# main.net
KiCad netlist of a schematic drawn in EAGLE
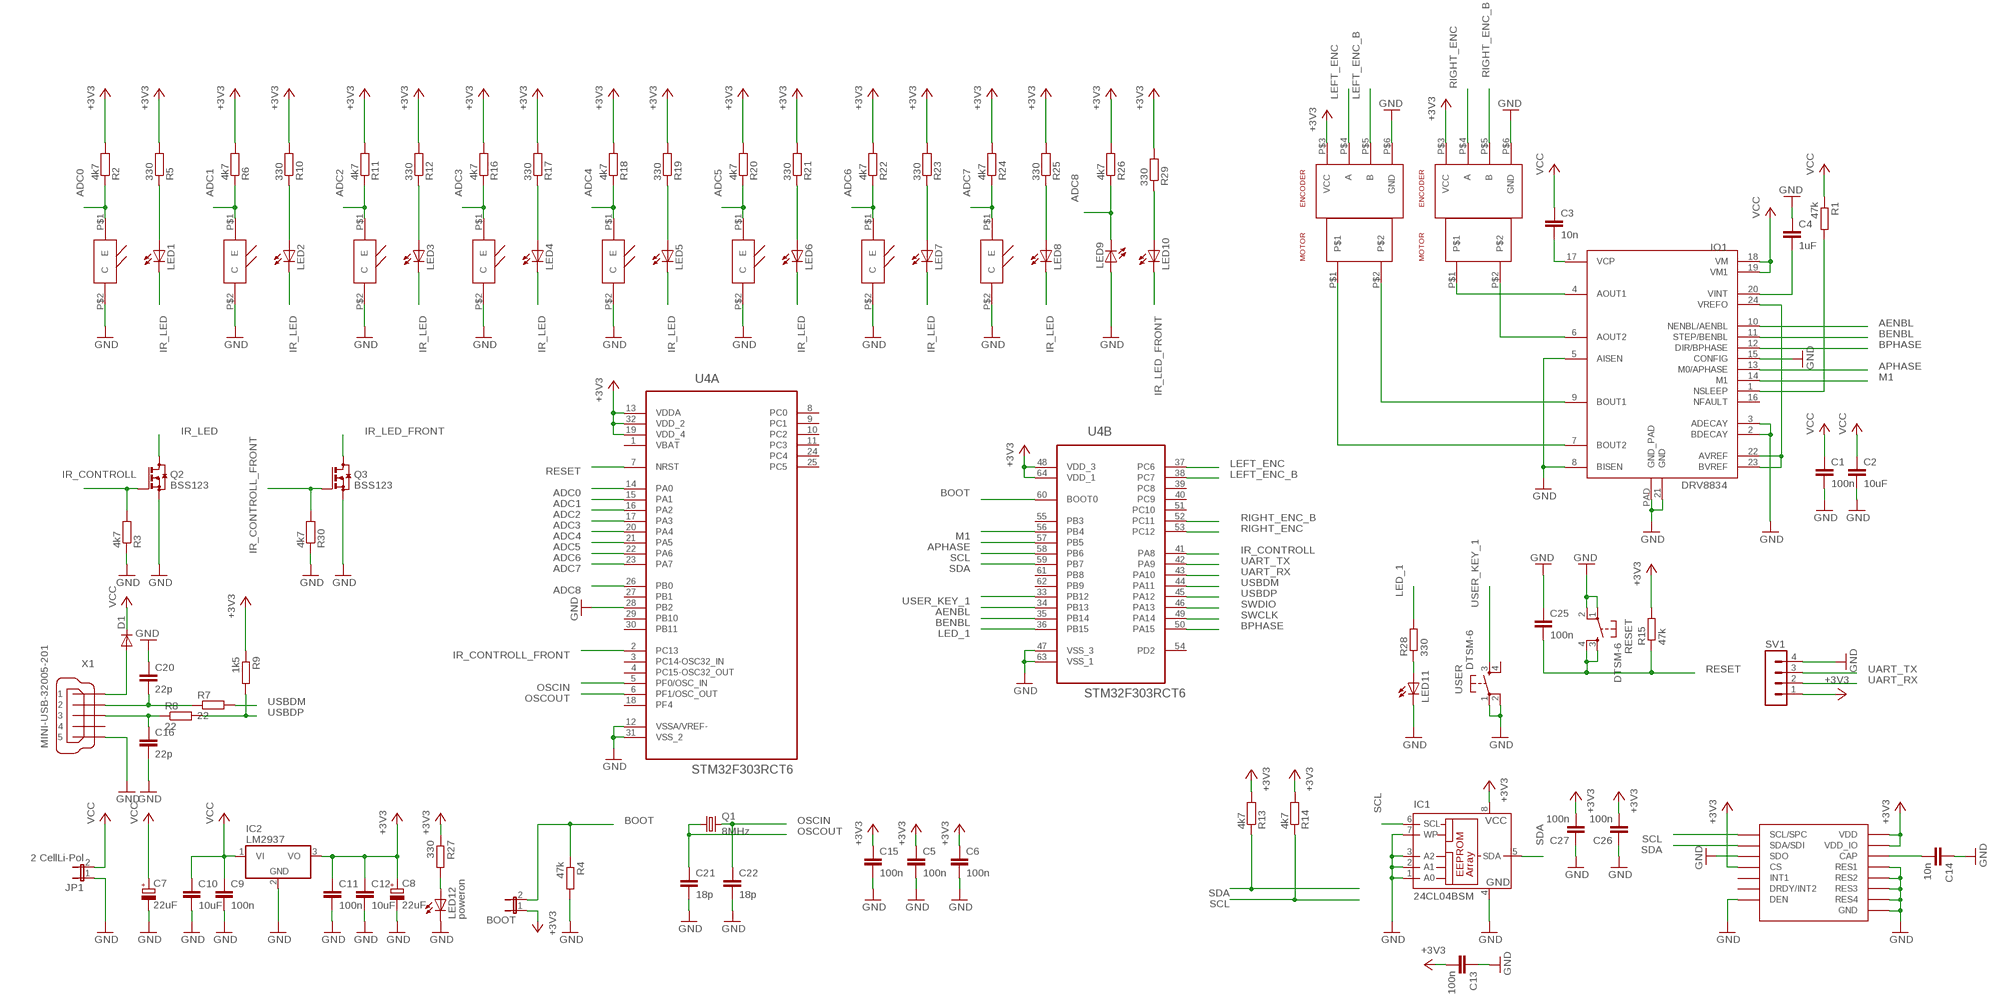
[diagram p0: schematic, sheet 1]

(export (version "E")
  (design (tool "Eeschema 10.0.6"))
  (components
    (comp (ref "BOOT")
      (value "JP1E")
      (footprint "eagle-import:JP1")
      (libsource (lib "eagle-import") (part "JP1E"))
    )
    (comp (ref "C1")
      (value "100n")
      (footprint "eagle-import:C1206")
      (libsource (lib "eagle-import") (part "C-EUC1206"))
    )
    (comp (ref "C2")
      (value "10uF")
      (footprint "eagle-import:C1206")
      (libsource (lib "eagle-import") (part "C-EUC1206"))
    )
    (comp (ref "C3")
      (value "10n")
      (footprint "eagle-import:C1206")
      (libsource (lib "eagle-import") (part "C-EUC1206"))
    )
    (comp (ref "C4")
      (value "1uF")
      (footprint "eagle-import:C1206")
      (libsource (lib "eagle-import") (part "C-EUC1206"))
    )
    (comp (ref "C5")
      (value "100n")
      (footprint "eagle-import:C0805")
      (libsource (lib "eagle-import") (part "C-EUC0805"))
    )
    (comp (ref "C6")
      (value "100n")
      (footprint "eagle-import:C0805")
      (libsource (lib "eagle-import") (part "C-EUC0805"))
    )
    (comp (ref "C7")
      (value "22uF")
      (footprint "eagle-import:153CLV-0505")
      (libsource (lib "eagle-import") (part "CPOL-EU153CLV-0505"))
    )
    (comp (ref "C8")
      (value "22uF")
      (footprint "eagle-import:153CLV-0505")
      (libsource (lib "eagle-import") (part "CPOL-EU153CLV-0505"))
    )
    (comp (ref "C9")
      (value "100n")
      (footprint "eagle-import:C0805")
      (libsource (lib "eagle-import") (part "C-EUC0805"))
    )
    (comp (ref "C10")
      (value "10uF")
      (footprint "eagle-import:C0805")
      (libsource (lib "eagle-import") (part "C-EUC0805"))
    )
    (comp (ref "C11")
      (value "100n")
      (footprint "eagle-import:C0805")
      (libsource (lib "eagle-import") (part "C-EUC0805"))
    )
    (comp (ref "C12")
      (value "10uF")
      (footprint "eagle-import:C0805")
      (libsource (lib "eagle-import") (part "C-EUC0805"))
    )
    (comp (ref "C13")
      (value "100n")
      (footprint "eagle-import:C0805")
      (libsource (lib "eagle-import") (part "C-EUC0805"))
    )
    (comp (ref "C14")
      (value "10n")
      (footprint "eagle-import:C0805")
      (libsource (lib "eagle-import") (part "C-EUC0805"))
    )
    (comp (ref "C15")
      (value "100n")
      (footprint "eagle-import:C0805")
      (libsource (lib "eagle-import") (part "C-EUC0805"))
    )
    (comp (ref "C16")
      (value "22p")
      (footprint "eagle-import:C0805")
      (libsource (lib "eagle-import") (part "C-EUC0805"))
    )
    (comp (ref "C20")
      (value "22p")
      (footprint "eagle-import:C0805")
      (libsource (lib "eagle-import") (part "C-EUC0805"))
    )
    (comp (ref "C21")
      (value "18p")
      (footprint "eagle-import:C0805")
      (libsource (lib "eagle-import") (part "C-EUC0805"))
    )
    (comp (ref "C22")
      (value "18p")
      (footprint "eagle-import:C0805")
      (libsource (lib "eagle-import") (part "C-EUC0805"))
    )
    (comp (ref "C25")
      (value "100n")
      (footprint "eagle-import:C0805")
      (libsource (lib "eagle-import") (part "C-EUC0805"))
    )
    (comp (ref "C26")
      (value "100n")
      (footprint "eagle-import:C0805")
      (libsource (lib "eagle-import") (part "C-EUC0805"))
    )
    (comp (ref "C27")
      (value "100n")
      (footprint "eagle-import:C0805")
      (libsource (lib "eagle-import") (part "C-EUC0805"))
    )
    (comp (ref "D1")
      (value "DIODE-SMB")
      (footprint "eagle-import:SMB")
      (libsource (lib "eagle-import") (part "DIODE-SMB"))
    )
    (comp (ref "IC1")
      (value "24CL04BSM")
      (footprint "eagle-import:SO-08M")
      (fields (field (name "MPN") "FM24CL04-S"))
      (libsource (lib "eagle-import") (part "24SMCL04B"))
    )
    (comp (ref "IC2")
      (value "LM2937")
      (footprint "eagle-import:TO263-3")
      (libsource (lib "eagle-import") (part "LM2937"))
    )
    (comp (ref "IO1")
      (value "DRV8834")
      (footprint "eagle-import:DRV8834_PCK")
      (libsource (lib "eagle-import") (part "DRV8834"))
    )
    (comp (ref "JP1")
      (value "2 CellLi-Pol")
      (footprint "eagle-import:JP1")
      (libsource (lib "eagle-import") (part "JP1E"))
    )
    (comp (ref "LED1")
      (value "LEDCHIPLED_1206")
      (footprint "eagle-import:CHIPLED_1206")
      (libsource (lib "eagle-import") (part "LEDCHIPLED_1206"))
    )
    (comp (ref "LED2")
      (value "LEDCHIPLED_1206")
      (footprint "eagle-import:CHIPLED_1206")
      (libsource (lib "eagle-import") (part "LEDCHIPLED_1206"))
    )
    (comp (ref "LED3")
      (value "LEDCHIPLED_1206")
      (footprint "eagle-import:CHIPLED_1206")
      (libsource (lib "eagle-import") (part "LEDCHIPLED_1206"))
    )
    (comp (ref "LED4")
      (value "LEDCHIPLED_1206")
      (footprint "eagle-import:CHIPLED_1206")
      (libsource (lib "eagle-import") (part "LEDCHIPLED_1206"))
    )
    (comp (ref "LED5")
      (value "LEDCHIPLED_1206")
      (footprint "eagle-import:CHIPLED_1206")
      (libsource (lib "eagle-import") (part "LEDCHIPLED_1206"))
    )
    (comp (ref "LED6")
      (value "LEDCHIPLED_1206")
      (footprint "eagle-import:CHIPLED_1206")
      (libsource (lib "eagle-import") (part "LEDCHIPLED_1206"))
    )
    (comp (ref "LED7")
      (value "LEDCHIPLED_1206")
      (footprint "eagle-import:CHIPLED_1206")
      (libsource (lib "eagle-import") (part "LEDCHIPLED_1206"))
    )
    (comp (ref "LED8")
      (value "LEDCHIPLED_1206")
      (footprint "eagle-import:CHIPLED_1206")
      (libsource (lib "eagle-import") (part "LEDCHIPLED_1206"))
    )
    (comp (ref "LED9")
      (value "LED5MM")
      (footprint "eagle-import:LED5MM")
      (libsource (lib "eagle-import") (part "my_parts_LED5MM"))
    )
    (comp (ref "LED10")
      (value "LED5MM")
      (footprint "eagle-import:LED5MM")
      (libsource (lib "eagle-import") (part "my_parts_LED5MM"))
    )
    (comp (ref "LED11")
      (value "LEDCHIPLED_1206")
      (footprint "eagle-import:CHIPLED_1206")
      (libsource (lib "eagle-import") (part "LEDCHIPLED_1206"))
    )
    (comp (ref "LED12")
      (value "poweron")
      (footprint "eagle-import:CHIPLED_1206")
      (libsource (lib "eagle-import") (part "LEDCHIPLED_1206"))
    )
    (comp (ref "LSM6DS0")
      (value "L3GD20H")
      (footprint "eagle-import:LGA16L")
      (libsource (lib "eagle-import") (part "L3GD20H"))
    )
    (comp (ref "Q1")
      (value "8MHz")
      (footprint "eagle-import:CTS406")
      (libsource (lib "eagle-import") (part "CRYSTALCTS406"))
    )
    (comp (ref "Q2")
      (value "BSS123")
      (footprint "eagle-import:SOT23")
      (libsource (lib "eagle-import") (part "BSS123"))
    )
    (comp (ref "Q3")
      (value "BSS123")
      (footprint "eagle-import:SOT23")
      (libsource (lib "eagle-import") (part "BSS123"))
    )
    (comp (ref "R1")
      (value "47k")
      (footprint "eagle-import:M1206")
      (libsource (lib "eagle-import") (part "R-EU_M1206"))
    )
    (comp (ref "R2")
      (value "4k7")
      (footprint "eagle-import:M0805")
      (libsource (lib "eagle-import") (part "R-EU_M0805"))
    )
    (comp (ref "R3")
      (value "4k7")
      (footprint "eagle-import:M0805")
      (libsource (lib "eagle-import") (part "R-EU_M0805"))
    )
    (comp (ref "R4")
      (value "47k")
      (footprint "eagle-import:M0805")
      (libsource (lib "eagle-import") (part "R-EU_M0805"))
    )
    (comp (ref "R5")
      (value "330")
      (footprint "eagle-import:M0805")
      (libsource (lib "eagle-import") (part "R-EU_M0805"))
    )
    (comp (ref "R6")
      (value "4k7")
      (footprint "eagle-import:M0805")
      (libsource (lib "eagle-import") (part "R-EU_M0805"))
    )
    (comp (ref "R7")
      (value "22")
      (footprint "eagle-import:M0805")
      (libsource (lib "eagle-import") (part "R-EU_M0805"))
    )
    (comp (ref "R8")
      (value "22")
      (footprint "eagle-import:M0805")
      (libsource (lib "eagle-import") (part "R-EU_M0805"))
    )
    (comp (ref "R9")
      (value "1k5")
      (footprint "eagle-import:M0805")
      (libsource (lib "eagle-import") (part "R-EU_M0805"))
    )
    (comp (ref "R10")
      (value "330")
      (footprint "eagle-import:M0805")
      (libsource (lib "eagle-import") (part "R-EU_M0805"))
    )
    (comp (ref "R11")
      (value "4k7")
      (footprint "eagle-import:M0805")
      (libsource (lib "eagle-import") (part "R-EU_M0805"))
    )
    (comp (ref "R12")
      (value "330")
      (footprint "eagle-import:M0805")
      (libsource (lib "eagle-import") (part "R-EU_M0805"))
    )
    (comp (ref "R13")
      (value "4k7")
      (footprint "eagle-import:M0805")
      (libsource (lib "eagle-import") (part "R-EU_M0805"))
    )
    (comp (ref "R14")
      (value "4k7")
      (footprint "eagle-import:M0805")
      (libsource (lib "eagle-import") (part "R-EU_M0805"))
    )
    (comp (ref "R15")
      (value "47k")
      (footprint "eagle-import:M0805")
      (libsource (lib "eagle-import") (part "R-EU_M0805"))
    )
    (comp (ref "R16")
      (value "4k7")
      (footprint "eagle-import:M0805")
      (libsource (lib "eagle-import") (part "R-EU_M0805"))
    )
    (comp (ref "R17")
      (value "330")
      (footprint "eagle-import:M0805")
      (libsource (lib "eagle-import") (part "R-EU_M0805"))
    )
    (comp (ref "R18")
      (value "4k7")
      (footprint "eagle-import:M0805")
      (libsource (lib "eagle-import") (part "R-EU_M0805"))
    )
    (comp (ref "R19")
      (value "330")
      (footprint "eagle-import:M0805")
      (libsource (lib "eagle-import") (part "R-EU_M0805"))
    )
    (comp (ref "R20")
      (value "4k7")
      (footprint "eagle-import:M0805")
      (libsource (lib "eagle-import") (part "R-EU_M0805"))
    )
    (comp (ref "R21")
      (value "330")
      (footprint "eagle-import:M0805")
      (libsource (lib "eagle-import") (part "R-EU_M0805"))
    )
    (comp (ref "R22")
      (value "4k7")
      (footprint "eagle-import:M0805")
      (libsource (lib "eagle-import") (part "R-EU_M0805"))
    )
    (comp (ref "R23")
      (value "330")
      (footprint "eagle-import:M0805")
      (libsource (lib "eagle-import") (part "R-EU_M0805"))
    )
    (comp (ref "R24")
      (value "4k7")
      (footprint "eagle-import:M0805")
      (libsource (lib "eagle-import") (part "R-EU_M0805"))
    )
    (comp (ref "R25")
      (value "330")
      (footprint "eagle-import:M0805")
      (libsource (lib "eagle-import") (part "R-EU_M0805"))
    )
    (comp (ref "R26")
      (value "4k7")
      (footprint "eagle-import:M0805")
      (libsource (lib "eagle-import") (part "R-EU_M0805"))
    )
    (comp (ref "R27")
      (value "330")
      (footprint "eagle-import:M0805")
      (libsource (lib "eagle-import") (part "R-EU_M0805"))
    )
    (comp (ref "R28")
      (value "330")
      (footprint "eagle-import:M0805")
      (libsource (lib "eagle-import") (part "R-EU_M0805"))
    )
    (comp (ref "R29")
      (value "330")
      (footprint "eagle-import:M0805")
      (libsource (lib "eagle-import") (part "R-EU_M0805"))
    )
    (comp (ref "R30")
      (value "4k7")
      (footprint "eagle-import:M0805")
      (libsource (lib "eagle-import") (part "R-EU_M0805"))
    )
    (comp (ref "RESET")
      (value "DTSM-6")
      (footprint "eagle-import:DTSM-6")
      (libsource (lib "eagle-import") (part "DTSM-6"))
    )
    (comp (ref "SV1")
      (value "MA04-1")
      (footprint "eagle-import:MA04-1")
      (libsource (lib "eagle-import") (part "MA04-1"))
    )
    (comp (ref "U$3")
      (value "SFH3710")
      (footprint "eagle-import:SFH3710")
      (libsource (lib "eagle-import") (part "SFH3710"))
    )
    (comp (ref "U$4")
      (value "SFH3710")
      (footprint "eagle-import:SFH3710")
      (libsource (lib "eagle-import") (part "SFH3710"))
    )
    (comp (ref "U$5")
      (value "SFH3710")
      (footprint "eagle-import:SFH3710")
      (libsource (lib "eagle-import") (part "SFH3710"))
    )
    (comp (ref "U$6")
      (value "SFH3710")
      (footprint "eagle-import:SFH3710")
      (libsource (lib "eagle-import") (part "SFH3710"))
    )
    (comp (ref "U$7")
      (value "SFH3710")
      (footprint "eagle-import:SFH3710")
      (libsource (lib "eagle-import") (part "SFH3710"))
    )
    (comp (ref "U$8")
      (value "SFH3710")
      (footprint "eagle-import:SFH3710")
      (libsource (lib "eagle-import") (part "SFH3710"))
    )
    (comp (ref "U$9")
      (value "SFH3710")
      (footprint "eagle-import:SFH3710")
      (libsource (lib "eagle-import") (part "SFH3710"))
    )
    (comp (ref "U$10")
      (value "SFH3710")
      (footprint "eagle-import:SFH3710")
      (libsource (lib "eagle-import") (part "SFH3710"))
    )
    (comp (ref "U$11")
      (value "POLOLU_GEAR_MOTORPOLO")
      (footprint "eagle-import:POLOLU_GEAR_MOTOR")
      (libsource (lib "eagle-import") (part "POLOLU_GEAR_MOTORPOLO"))
    )
    (comp (ref "U$12")
      (value "POLOLU_GEAR_MOTORPOLO")
      (footprint "eagle-import:POLOLU_GEAR_MOTOR")
      (libsource (lib "eagle-import") (part "POLOLU_GEAR_MOTORPOLO"))
    )
    (comp (ref "U4")
      (value "STM32F303RCT6")
      (footprint "eagle-import:QFP50P1200X1200X160-64N")
      (libsource (lib "eagle-import") (part "STM32F303RCT6"))
    )
    (comp (ref "USER")
      (value "DTSM-6")
      (footprint "eagle-import:DTSM-6")
      (libsource (lib "eagle-import") (part "DTSM-6"))
    )
    (comp (ref "X1")
      (value "MINI-USB-32005-201")
      (footprint "eagle-import:32005-201")
      (libsource (lib "eagle-import") (part "MINI-USB-32005-201"))
    )
  )
  (nets
    (net (code "1") (name "+3V3") (class "Default")
      (node (ref "BOOT") (pin "1") (pinfunction "1_1") (pintype "passive"))
      (node (ref "C11") (pin "1") (pinfunction "1_1") (pintype "passive"))
      (node (ref "C12") (pin "1") (pinfunction "1_1") (pintype "passive"))
      (node (ref "C13") (pin "2") (pinfunction "2_2") (pintype "passive"))
      (node (ref "C15") (pin "1") (pinfunction "1_1") (pintype "passive"))
      (node (ref "C26") (pin "2") (pinfunction "2_2") (pintype "passive"))
      (node (ref "C27") (pin "2") (pinfunction "2_2") (pintype "passive"))
      (node (ref "C5") (pin "1") (pinfunction "1_1") (pintype "passive"))
      (node (ref "C6") (pin "1") (pinfunction "1_1") (pintype "passive"))
      (node (ref "C8") (pin "+") (pinfunction "+_+") (pintype "passive"))
      (node (ref "IC1") (pin "8") (pinfunction "VCC_8") (pintype "power_in"))
      (node (ref "IC2") (pin "3") (pinfunction "VO_3") (pintype "passive"))
      (node (ref "LSM6DS0") (pin "P$1") (pinfunction "VDD_IO_P$1") (pintype "power_in"))
      (node (ref "LSM6DS0") (pin "P$16") (pinfunction "VDD_P$16") (pintype "power_in"))
      (node (ref "LSM6DS0") (pin "P$5") (pinfunction "CS_P$5") (pintype "bidirectional"))
      (node (ref "R10") (pin "2") (pinfunction "2_2") (pintype "passive"))
      (node (ref "R11") (pin "2") (pinfunction "2_2") (pintype "passive"))
      (node (ref "R12") (pin "2") (pinfunction "2_2") (pintype "passive"))
      (node (ref "R13") (pin "2") (pinfunction "2_2") (pintype "passive"))
      (node (ref "R14") (pin "2") (pinfunction "2_2") (pintype "passive"))
      (node (ref "R15") (pin "2") (pinfunction "2_2") (pintype "passive"))
      (node (ref "R16") (pin "2") (pinfunction "2_2") (pintype "passive"))
      (node (ref "R17") (pin "2") (pinfunction "2_2") (pintype "passive"))
      (node (ref "R18") (pin "2") (pinfunction "2_2") (pintype "passive"))
      (node (ref "R19") (pin "2") (pinfunction "2_2") (pintype "passive"))
      (node (ref "R2") (pin "2") (pinfunction "2_2") (pintype "passive"))
      (node (ref "R20") (pin "2") (pinfunction "2_2") (pintype "passive"))
      (node (ref "R21") (pin "2") (pinfunction "2_2") (pintype "passive"))
      (node (ref "R22") (pin "2") (pinfunction "2_2") (pintype "passive"))
      (node (ref "R23") (pin "2") (pinfunction "2_2") (pintype "passive"))
      (node (ref "R24") (pin "2") (pinfunction "2_2") (pintype "passive"))
      (node (ref "R25") (pin "2") (pinfunction "2_2") (pintype "passive"))
      (node (ref "R26") (pin "2") (pinfunction "2_2") (pintype "passive"))
      (node (ref "R27") (pin "1") (pinfunction "1_1") (pintype "passive"))
      (node (ref "R29") (pin "2") (pinfunction "2_2") (pintype "passive"))
      (node (ref "R5") (pin "2") (pinfunction "2_2") (pintype "passive"))
      (node (ref "R6") (pin "2") (pinfunction "2_2") (pintype "passive"))
      (node (ref "R9") (pin "1") (pinfunction "1_1") (pintype "passive"))
      (node (ref "SV1") (pin "1") (pinfunction "1_1") (pintype "passive"))
      (node (ref "U$11") (pin "P$3") (pinfunction "VCC_P$3") (pintype "bidirectional"))
      (node (ref "U$12") (pin "P$3") (pinfunction "VCC_P$3") (pintype "bidirectional"))
      (node (ref "U4") (pin "13") (pinfunction "VDDA_13") (pintype "power_in"))
      (node (ref "U4") (pin "19") (pinfunction "VDD_4_19") (pintype "power_in"))
      (node (ref "U4") (pin "32") (pinfunction "VDD_2_32") (pintype "power_in"))
      (node (ref "U4") (pin "48") (pinfunction "VDD_3_48") (pintype "power_in"))
      (node (ref "U4") (pin "64") (pinfunction "VDD_1_64") (pintype "power_in"))
    )
    (net (code "2") (name "/ADC0") (class "Default")
      (node (ref "R2") (pin "1") (pinfunction "1_1") (pintype "passive"))
      (node (ref "U$3") (pin "P$1") (pinfunction "E_P$1") (pintype "bidirectional"))
      (node (ref "U4") (pin "14") (pinfunction "PA0_14") (pintype "bidirectional"))
    )
    (net (code "3") (name "/ADC1") (class "Default")
      (node (ref "R6") (pin "1") (pinfunction "1_1") (pintype "passive"))
      (node (ref "U$4") (pin "P$1") (pinfunction "E_P$1") (pintype "bidirectional"))
      (node (ref "U4") (pin "15") (pinfunction "PA1_15") (pintype "bidirectional"))
    )
    (net (code "4") (name "/ADC2") (class "Default")
      (node (ref "R11") (pin "1") (pinfunction "1_1") (pintype "passive"))
      (node (ref "U$5") (pin "P$1") (pinfunction "E_P$1") (pintype "bidirectional"))
      (node (ref "U4") (pin "16") (pinfunction "PA2_16") (pintype "bidirectional"))
    )
    (net (code "5") (name "/ADC3") (class "Default")
      (node (ref "R16") (pin "1") (pinfunction "1_1") (pintype "passive"))
      (node (ref "U$6") (pin "P$1") (pinfunction "E_P$1") (pintype "bidirectional"))
      (node (ref "U4") (pin "17") (pinfunction "PA3_17") (pintype "bidirectional"))
    )
    (net (code "6") (name "/ADC4") (class "Default")
      (node (ref "R18") (pin "1") (pinfunction "1_1") (pintype "passive"))
      (node (ref "U$7") (pin "P$1") (pinfunction "E_P$1") (pintype "bidirectional"))
      (node (ref "U4") (pin "20") (pinfunction "PA4_20") (pintype "bidirectional"))
    )
    (net (code "7") (name "/ADC5") (class "Default")
      (node (ref "R20") (pin "1") (pinfunction "1_1") (pintype "passive"))
      (node (ref "U$8") (pin "P$1") (pinfunction "E_P$1") (pintype "bidirectional"))
      (node (ref "U4") (pin "21") (pinfunction "PA5_21") (pintype "bidirectional"))
    )
    (net (code "8") (name "/ADC6") (class "Default")
      (node (ref "R22") (pin "1") (pinfunction "1_1") (pintype "passive"))
      (node (ref "U$9") (pin "P$1") (pinfunction "E_P$1") (pintype "bidirectional"))
      (node (ref "U4") (pin "22") (pinfunction "PA6_22") (pintype "bidirectional"))
    )
    (net (code "9") (name "/ADC7") (class "Default")
      (node (ref "R24") (pin "1") (pinfunction "1_1") (pintype "passive"))
      (node (ref "U$10") (pin "P$1") (pinfunction "E_P$1") (pintype "bidirectional"))
      (node (ref "U4") (pin "23") (pinfunction "PA7_23") (pintype "bidirectional"))
    )
    (net (code "10") (name "/ADC8") (class "Default")
      (node (ref "LED9") (pin "K") (pinfunction "C_K") (pintype "passive"))
      (node (ref "R26") (pin "1") (pinfunction "1_1") (pintype "passive"))
      (node (ref "U4") (pin "26") (pinfunction "PB0_26") (pintype "bidirectional"))
    )
    (net (code "11") (name "/AENBL") (class "Default")
      (node (ref "IO1") (pin "10") (pinfunction "NENBL/AENBL_10") (pintype "bidirectional"))
      (node (ref "U4") (pin "34") (pinfunction "PB13_34") (pintype "bidirectional"))
    )
    (net (code "12") (name "/APHASE") (class "Default")
      (node (ref "IO1") (pin "13") (pinfunction "M0/APHASE_13") (pintype "bidirectional"))
      (node (ref "U4") (pin "57") (pinfunction "PB5_57") (pintype "bidirectional"))
    )
    (net (code "13") (name "/BENBL") (class "Default")
      (node (ref "IO1") (pin "11") (pinfunction "STEP/BENBL_11") (pintype "bidirectional"))
      (node (ref "U4") (pin "35") (pinfunction "PB14_35") (pintype "bidirectional"))
    )
    (net (code "14") (name "/BOOT") (class "Default")
      (node (ref "BOOT") (pin "2") (pinfunction "2_2") (pintype "passive"))
      (node (ref "R4") (pin "1") (pinfunction "1_1") (pintype "passive"))
      (node (ref "U4") (pin "60") (pinfunction "BOOT0_60") (pintype "input"))
    )
    (net (code "15") (name "/BPHASE") (class "Default")
      (node (ref "IO1") (pin "12") (pinfunction "DIR/BPHASE_12") (pintype "bidirectional"))
      (node (ref "U4") (pin "50") (pinfunction "PA15_50") (pintype "bidirectional"))
    )
    (net (code "16") (name "/IR_CONTROLL") (class "Default")
      (node (ref "Q2") (pin "1") (pinfunction "G_1") (pintype "passive"))
      (node (ref "R3") (pin "2") (pinfunction "2_2") (pintype "passive"))
      (node (ref "U4") (pin "41") (pinfunction "PA8_41") (pintype "bidirectional"))
    )
    (net (code "17") (name "/IR_CONTROLL_FRONT") (class "Default")
      (node (ref "Q3") (pin "1") (pinfunction "G_1") (pintype "passive"))
      (node (ref "R30") (pin "2") (pinfunction "2_2") (pintype "passive"))
      (node (ref "U4") (pin "2") (pinfunction "PC13_2") (pintype "bidirectional"))
    )
    (net (code "18") (name "/IR_LED") (class "Default")
      (node (ref "LED1") (pin "C") (pinfunction "C_C") (pintype "passive"))
      (node (ref "LED2") (pin "C") (pinfunction "C_C") (pintype "passive"))
      (node (ref "LED3") (pin "C") (pinfunction "C_C") (pintype "passive"))
      (node (ref "LED4") (pin "C") (pinfunction "C_C") (pintype "passive"))
      (node (ref "LED5") (pin "C") (pinfunction "C_C") (pintype "passive"))
      (node (ref "LED6") (pin "C") (pinfunction "C_C") (pintype "passive"))
      (node (ref "LED7") (pin "C") (pinfunction "C_C") (pintype "passive"))
      (node (ref "LED8") (pin "C") (pinfunction "C_C") (pintype "passive"))
      (node (ref "Q2") (pin "3") (pinfunction "D_3") (pintype "passive"))
    )
    (net (code "19") (name "/IR_LED_FRONT") (class "Default")
      (node (ref "LED10") (pin "K") (pinfunction "C_K") (pintype "passive"))
      (node (ref "Q3") (pin "3") (pinfunction "D_3") (pintype "passive"))
    )
    (net (code "20") (name "/LED_1") (class "Default")
      (node (ref "R28") (pin "2") (pinfunction "2_2") (pintype "passive"))
      (node (ref "U4") (pin "36") (pinfunction "PB15_36") (pintype "bidirectional"))
    )
    (net (code "21") (name "/LEFT_ENC") (class "Default")
      (node (ref "U$11") (pin "P$4") (pinfunction "A_P$4") (pintype "bidirectional"))
      (node (ref "U4") (pin "37") (pinfunction "PC6_37") (pintype "bidirectional"))
    )
    (net (code "22") (name "/LEFT_ENC_B") (class "Default")
      (node (ref "U$11") (pin "P$5") (pinfunction "B_P$5") (pintype "bidirectional"))
      (node (ref "U4") (pin "38") (pinfunction "PC7_38") (pintype "bidirectional"))
    )
    (net (code "23") (name "/M1") (class "Default")
      (node (ref "IO1") (pin "14") (pinfunction "M1_14") (pintype "bidirectional"))
      (node (ref "U4") (pin "56") (pinfunction "PB4_56") (pintype "bidirectional"))
    )
    (net (code "24") (name "/OSCIN") (class "Default")
      (node (ref "C22") (pin "1") (pinfunction "1_1") (pintype "passive"))
      (node (ref "Q1") (pin "3") (pinfunction "2_3") (pintype "passive"))
      (node (ref "U4") (pin "5") (pinfunction "PF0/OSC_IN_5") (pintype "bidirectional"))
    )
    (net (code "25") (name "/OSCOUT") (class "Default")
      (node (ref "C21") (pin "1") (pinfunction "1_1") (pintype "passive"))
      (node (ref "Q1") (pin "1") (pinfunction "1_1") (pintype "passive"))
      (node (ref "U4") (pin "6") (pinfunction "PF1/OSC_OUT_6") (pintype "bidirectional"))
    )
    (net (code "26") (name "/RESET") (class "Default")
      (node (ref "C25") (pin "2") (pinfunction "2_2") (pintype "passive"))
      (node (ref "R15") (pin "1") (pinfunction "1_1") (pintype "passive"))
      (node (ref "RESET") (pin "3") (pinfunction "3_3") (pintype "passive"))
      (node (ref "RESET") (pin "4") (pinfunction "4_4") (pintype "passive"))
      (node (ref "U4") (pin "7") (pinfunction "NRST_7") (pintype "bidirectional"))
    )
    (net (code "27") (name "/RIGHT_ENC") (class "Default")
      (node (ref "U$12") (pin "P$4") (pinfunction "A_P$4") (pintype "bidirectional"))
      (node (ref "U4") (pin "53") (pinfunction "PC12_53") (pintype "bidirectional"))
    )
    (net (code "28") (name "/RIGHT_ENC_B") (class "Default")
      (node (ref "U$12") (pin "P$5") (pinfunction "B_P$5") (pintype "bidirectional"))
      (node (ref "U4") (pin "52") (pinfunction "PC11_52") (pintype "bidirectional"))
    )
    (net (code "29") (name "/SCL") (class "Default")
      (node (ref "IC1") (pin "6") (pinfunction "SCL_6") (pintype "input"))
      (node (ref "LSM6DS0") (pin "P$2") (pinfunction "SCL/SPC_P$2") (pintype "bidirectional"))
      (node (ref "R14") (pin "1") (pinfunction "1_1") (pintype "passive"))
      (node (ref "U4") (pin "58") (pinfunction "PB6_58") (pintype "bidirectional"))
    )
    (net (code "30") (name "/SDA") (class "Default")
      (node (ref "IC1") (pin "5") (pinfunction "SDA_5") (pintype "bidirectional"))
      (node (ref "LSM6DS0") (pin "P$3") (pinfunction "SDA/SDI_P$3") (pintype "bidirectional"))
      (node (ref "R13") (pin "1") (pinfunction "1_1") (pintype "passive"))
      (node (ref "U4") (pin "59") (pinfunction "PB7_59") (pintype "bidirectional"))
    )
    (net (code "31") (name "/SWCLK") (class "Default")
      (node (ref "U4") (pin "49") (pinfunction "PA14_49") (pintype "bidirectional"))
    )
    (net (code "32") (name "/SWDIO") (class "Default")
      (node (ref "U4") (pin "46") (pinfunction "PA13_46") (pintype "bidirectional"))
    )
    (net (code "33") (name "/UART_RX") (class "Default")
      (node (ref "SV1") (pin "2") (pinfunction "2_2") (pintype "passive"))
      (node (ref "U4") (pin "43") (pinfunction "PA10_43") (pintype "bidirectional"))
    )
    (net (code "34") (name "/UART_TX") (class "Default")
      (node (ref "SV1") (pin "3") (pinfunction "3_3") (pintype "passive"))
      (node (ref "U4") (pin "42") (pinfunction "PA9_42") (pintype "bidirectional"))
    )
    (net (code "35") (name "/USBDM") (class "Default")
      (node (ref "R7") (pin "2") (pinfunction "2_2") (pintype "passive"))
      (node (ref "U4") (pin "44") (pinfunction "PA11_44") (pintype "bidirectional"))
    )
    (net (code "36") (name "/USBDP") (class "Default")
      (node (ref "R8") (pin "2") (pinfunction "2_2") (pintype "passive"))
      (node (ref "R9") (pin "2") (pinfunction "2_2") (pintype "passive"))
      (node (ref "U4") (pin "45") (pinfunction "PA12_45") (pintype "bidirectional"))
    )
    (net (code "37") (name "/USER_KEY_1") (class "Default")
      (node (ref "U4") (pin "33") (pinfunction "PB12_33") (pintype "bidirectional"))
      (node (ref "USER") (pin "3") (pinfunction "3_3") (pintype "passive"))
    )
    (net (code "38") (name "/VBAT") (class "Default")
      (node (ref "U4") (pin "1") (pinfunction "VBAT_1") (pintype "power_in"))
    )
    (net (code "39") (name "GND") (class "Default")
      (node (ref "C1") (pin "2") (pinfunction "2_2") (pintype "passive"))
      (node (ref "C10") (pin "2") (pinfunction "2_2") (pintype "passive"))
      (node (ref "C11") (pin "2") (pinfunction "2_2") (pintype "passive"))
      (node (ref "C12") (pin "2") (pinfunction "2_2") (pintype "passive"))
      (node (ref "C13") (pin "1") (pinfunction "1_1") (pintype "passive"))
      (node (ref "C14") (pin "1") (pinfunction "1_1") (pintype "passive"))
      (node (ref "C15") (pin "2") (pinfunction "2_2") (pintype "passive"))
      (node (ref "C16") (pin "2") (pinfunction "2_2") (pintype "passive"))
      (node (ref "C2") (pin "2") (pinfunction "2_2") (pintype "passive"))
      (node (ref "C20") (pin "1") (pinfunction "1_1") (pintype "passive"))
      (node (ref "C21") (pin "2") (pinfunction "2_2") (pintype "passive"))
      (node (ref "C22") (pin "2") (pinfunction "2_2") (pintype "passive"))
      (node (ref "C25") (pin "1") (pinfunction "1_1") (pintype "passive"))
      (node (ref "C26") (pin "1") (pinfunction "1_1") (pintype "passive"))
      (node (ref "C27") (pin "1") (pinfunction "1_1") (pintype "passive"))
      (node (ref "C4") (pin "1") (pinfunction "1_1") (pintype "passive"))
      (node (ref "C5") (pin "2") (pinfunction "2_2") (pintype "passive"))
      (node (ref "C6") (pin "2") (pinfunction "2_2") (pintype "passive"))
      (node (ref "C7") (pin "-") (pinfunction "-_-") (pintype "passive"))
      (node (ref "C8") (pin "-") (pinfunction "-_-") (pintype "passive"))
      (node (ref "C9") (pin "2") (pinfunction "2_2") (pintype "passive"))
      (node (ref "IC1") (pin "1") (pinfunction "A0_1") (pintype "input"))
      (node (ref "IC1") (pin "2") (pinfunction "A1_2") (pintype "input"))
      (node (ref "IC1") (pin "3") (pinfunction "A2_3") (pintype "input"))
      (node (ref "IC1") (pin "4") (pinfunction "GND_4") (pintype "power_in"))
      (node (ref "IC1") (pin "7") (pinfunction "WP_7") (pintype "input"))
      (node (ref "IC2") (pin "2") (pinfunction "GND_2") (pintype "passive"))
      (node (ref "IO1") (pin "15") (pinfunction "CONFIG_15") (pintype "bidirectional"))
      (node (ref "IO1") (pin "2") (pinfunction "BDECAY_2") (pintype "bidirectional"))
      (node (ref "IO1") (pin "21") (pinfunction "GND_21") (pintype "bidirectional"))
      (node (ref "IO1") (pin "3") (pinfunction "ADECAY_3") (pintype "bidirectional"))
      (node (ref "IO1") (pin "5") (pinfunction "AISEN_5") (pintype "bidirectional"))
      (node (ref "IO1") (pin "8") (pinfunction "BISEN_8") (pintype "bidirectional"))
      (node (ref "IO1") (pin "PAD") (pinfunction "GND_PAD_PAD") (pintype "bidirectional"))
      (node (ref "JP1") (pin "1") (pinfunction "1_1") (pintype "passive"))
      (node (ref "LED11") (pin "C") (pinfunction "C_C") (pintype "passive"))
      (node (ref "LED12") (pin "C") (pinfunction "C_C") (pintype "passive"))
      (node (ref "LED9") (pin "A") (pinfunction "A_A") (pintype "passive"))
      (node (ref "LSM6DS0") (pin "P$10") (pinfunction "RES2_P$10") (pintype "bidirectional"))
      (node (ref "LSM6DS0") (pin "P$11") (pinfunction "RES3_P$11") (pintype "bidirectional"))
      (node (ref "LSM6DS0") (pin "P$12") (pinfunction "GND_P$12") (pintype "power_in"))
      (node (ref "LSM6DS0") (pin "P$13") (pinfunction "GND_P$13") (pintype "power_in"))
      (node (ref "LSM6DS0") (pin "P$15") (pinfunction "RES4_P$15") (pintype "bidirectional"))
      (node (ref "LSM6DS0") (pin "P$4") (pinfunction "SDO_P$4") (pintype "bidirectional"))
      (node (ref "LSM6DS0") (pin "P$8") (pinfunction "DEN_P$8") (pintype "bidirectional"))
      (node (ref "LSM6DS0") (pin "P$9") (pinfunction "RES1_P$9") (pintype "bidirectional"))
      (node (ref "Q2") (pin "2") (pinfunction "S_2") (pintype "passive"))
      (node (ref "Q3") (pin "2") (pinfunction "S_2") (pintype "passive"))
      (node (ref "R3") (pin "1") (pinfunction "1_1") (pintype "passive"))
      (node (ref "R30") (pin "1") (pinfunction "1_1") (pintype "passive"))
      (node (ref "R4") (pin "2") (pinfunction "2_2") (pintype "passive"))
      (node (ref "RESET") (pin "1") (pinfunction "1_1") (pintype "passive"))
      (node (ref "RESET") (pin "2") (pinfunction "2_2") (pintype "passive"))
      (node (ref "SV1") (pin "4") (pinfunction "4_4") (pintype "passive"))
      (node (ref "U$10") (pin "P$2") (pinfunction "C_P$2") (pintype "bidirectional"))
      (node (ref "U$11") (pin "P$6") (pinfunction "GND_P$6") (pintype "bidirectional"))
      (node (ref "U$12") (pin "P$6") (pinfunction "GND_P$6") (pintype "bidirectional"))
      (node (ref "U$3") (pin "P$2") (pinfunction "C_P$2") (pintype "bidirectional"))
      (node (ref "U$4") (pin "P$2") (pinfunction "C_P$2") (pintype "bidirectional"))
      (node (ref "U$5") (pin "P$2") (pinfunction "C_P$2") (pintype "bidirectional"))
      (node (ref "U$6") (pin "P$2") (pinfunction "C_P$2") (pintype "bidirectional"))
      (node (ref "U$7") (pin "P$2") (pinfunction "C_P$2") (pintype "bidirectional"))
      (node (ref "U$8") (pin "P$2") (pinfunction "C_P$2") (pintype "bidirectional"))
      (node (ref "U$9") (pin "P$2") (pinfunction "C_P$2") (pintype "bidirectional"))
      (node (ref "U4") (pin "12") (pinfunction "VSSA/VREF-_12") (pintype "power_in"))
      (node (ref "U4") (pin "28") (pinfunction "PB2_28") (pintype "bidirectional"))
      (node (ref "U4") (pin "31") (pinfunction "VSS_2_31") (pintype "passive"))
      (node (ref "U4") (pin "47") (pinfunction "VSS_3_47") (pintype "passive"))
      (node (ref "U4") (pin "63") (pinfunction "VSS_1_63") (pintype "passive"))
      (node (ref "USER") (pin "1") (pinfunction "1_1") (pintype "passive"))
      (node (ref "USER") (pin "2") (pinfunction "2_2") (pintype "passive"))
      (node (ref "X1") (pin "5") (pinfunction "5_5") (pintype "passive"))
    )
    (net (code "40") (name "Net-(C16-Pad1)") (class "Default")
      (node (ref "C16") (pin "1") (pinfunction "1_1") (pintype "passive"))
      (node (ref "R8") (pin "1") (pinfunction "1_1") (pintype "passive"))
      (node (ref "X1") (pin "3") (pinfunction "3_3") (pintype "passive"))
    )
    (net (code "41") (name "Net-(C20-Pad2)") (class "Default")
      (node (ref "C20") (pin "2") (pinfunction "2_2") (pintype "passive"))
      (node (ref "R7") (pin "1") (pinfunction "1_1") (pintype "passive"))
      (node (ref "X1") (pin "2") (pinfunction "2_2") (pintype "passive"))
    )
    (net (code "42") (name "Net-(D1-PadA)") (class "Default")
      (node (ref "D1") (pin "A") (pinfunction "A_A") (pintype "passive"))
      (node (ref "X1") (pin "1") (pinfunction "1_1") (pintype "passive"))
    )
    (net (code "43") (name "Net-(IO1-AOUT1)") (class "Default")
      (node (ref "IO1") (pin "4") (pinfunction "AOUT1_4") (pintype "bidirectional"))
      (node (ref "U$12") (pin "P$1") (pinfunction "P$1_P$1") (pintype "bidirectional"))
    )
    (net (code "44") (name "Net-(IO1-AOUT2)") (class "Default")
      (node (ref "IO1") (pin "6") (pinfunction "AOUT2_6") (pintype "bidirectional"))
      (node (ref "U$12") (pin "P$2") (pinfunction "P$2_P$2") (pintype "bidirectional"))
    )
    (net (code "45") (name "Net-(IO1-AVREF)") (class "Default")
      (node (ref "IO1") (pin "22") (pinfunction "AVREF_22") (pintype "bidirectional"))
      (node (ref "IO1") (pin "23") (pinfunction "BVREF_23") (pintype "bidirectional"))
      (node (ref "IO1") (pin "24") (pinfunction "VREFO_24") (pintype "bidirectional"))
    )
    (net (code "46") (name "Net-(IO1-BOUT1)") (class "Default")
      (node (ref "IO1") (pin "9") (pinfunction "BOUT1_9") (pintype "bidirectional"))
      (node (ref "U$11") (pin "P$2") (pinfunction "P$2_P$2") (pintype "bidirectional"))
    )
    (net (code "47") (name "Net-(IO1-BOUT2)") (class "Default")
      (node (ref "IO1") (pin "7") (pinfunction "BOUT2_7") (pintype "bidirectional"))
      (node (ref "U$11") (pin "P$1") (pinfunction "P$1_P$1") (pintype "bidirectional"))
    )
    (net (code "48") (name "Net-(IO1-NSLEEP)") (class "Default")
      (node (ref "IO1") (pin "1") (pinfunction "NSLEEP_1") (pintype "bidirectional"))
      (node (ref "R1") (pin "2") (pinfunction "2_2") (pintype "passive"))
    )
    (net (code "49") (name "Net-(IO1-VCP)") (class "Default")
      (node (ref "C3") (pin "2") (pinfunction "2_2") (pintype "passive"))
      (node (ref "IO1") (pin "17") (pinfunction "VCP_17") (pintype "bidirectional"))
    )
    (net (code "50") (name "Net-(IO1-VINT)") (class "Default")
      (node (ref "C4") (pin "2") (pinfunction "2_2") (pintype "passive"))
      (node (ref "IO1") (pin "20") (pinfunction "VINT_20") (pintype "bidirectional"))
    )
    (net (code "51") (name "Net-(LED1-PadA)") (class "Default")
      (node (ref "LED1") (pin "A") (pinfunction "A_A") (pintype "passive"))
      (node (ref "R5") (pin "1") (pinfunction "1_1") (pintype "passive"))
    )
    (net (code "52") (name "Net-(LED2-PadA)") (class "Default")
      (node (ref "LED2") (pin "A") (pinfunction "A_A") (pintype "passive"))
      (node (ref "R10") (pin "1") (pinfunction "1_1") (pintype "passive"))
    )
    (net (code "53") (name "Net-(LED3-PadA)") (class "Default")
      (node (ref "LED3") (pin "A") (pinfunction "A_A") (pintype "passive"))
      (node (ref "R12") (pin "1") (pinfunction "1_1") (pintype "passive"))
    )
    (net (code "54") (name "Net-(LED4-PadA)") (class "Default")
      (node (ref "LED4") (pin "A") (pinfunction "A_A") (pintype "passive"))
      (node (ref "R17") (pin "1") (pinfunction "1_1") (pintype "passive"))
    )
    (net (code "55") (name "Net-(LED5-PadA)") (class "Default")
      (node (ref "LED5") (pin "A") (pinfunction "A_A") (pintype "passive"))
      (node (ref "R19") (pin "1") (pinfunction "1_1") (pintype "passive"))
    )
    (net (code "56") (name "Net-(LED6-PadA)") (class "Default")
      (node (ref "LED6") (pin "A") (pinfunction "A_A") (pintype "passive"))
      (node (ref "R21") (pin "1") (pinfunction "1_1") (pintype "passive"))
    )
    (net (code "57") (name "Net-(LED7-PadA)") (class "Default")
      (node (ref "LED7") (pin "A") (pinfunction "A_A") (pintype "passive"))
      (node (ref "R23") (pin "1") (pinfunction "1_1") (pintype "passive"))
    )
    (net (code "58") (name "Net-(LED8-PadA)") (class "Default")
      (node (ref "LED8") (pin "A") (pinfunction "A_A") (pintype "passive"))
      (node (ref "R25") (pin "1") (pinfunction "1_1") (pintype "passive"))
    )
    (net (code "59") (name "Net-(LED10-PadA)") (class "Default")
      (node (ref "LED10") (pin "A") (pinfunction "A_A") (pintype "passive"))
      (node (ref "R29") (pin "1") (pinfunction "1_1") (pintype "passive"))
    )
    (net (code "60") (name "Net-(LED11-PadA)") (class "Default")
      (node (ref "LED11") (pin "A") (pinfunction "A_A") (pintype "passive"))
      (node (ref "R28") (pin "1") (pinfunction "1_1") (pintype "passive"))
    )
    (net (code "61") (name "Net-(LED12-PadA)") (class "Default")
      (node (ref "LED12") (pin "A") (pinfunction "A_A") (pintype "passive"))
      (node (ref "R27") (pin "2") (pinfunction "2_2") (pintype "passive"))
    )
    (net (code "62") (name "Net-(LSM6DS0-CAP)") (class "Default")
      (node (ref "C14") (pin "2") (pinfunction "2_2") (pintype "passive"))
      (node (ref "LSM6DS0") (pin "P$14") (pinfunction "CAP_P$14") (pintype "bidirectional"))
    )
    (net (code "63") (name "VCC") (class "Default")
      (node (ref "C1") (pin "1") (pinfunction "1_1") (pintype "passive"))
      (node (ref "C10") (pin "1") (pinfunction "1_1") (pintype "passive"))
      (node (ref "C2") (pin "1") (pinfunction "1_1") (pintype "passive"))
      (node (ref "C3") (pin "1") (pinfunction "1_1") (pintype "passive"))
      (node (ref "C7") (pin "+") (pinfunction "+_+") (pintype "passive"))
      (node (ref "C9") (pin "1") (pinfunction "1_1") (pintype "passive"))
      (node (ref "D1") (pin "C") (pinfunction "C_C") (pintype "passive"))
      (node (ref "IC2") (pin "1") (pinfunction "VI_1") (pintype "input"))
      (node (ref "IO1") (pin "18") (pinfunction "VM_18") (pintype "bidirectional"))
      (node (ref "IO1") (pin "19") (pinfunction "VM1_19") (pintype "bidirectional"))
      (node (ref "JP1") (pin "2") (pinfunction "2_2") (pintype "passive"))
      (node (ref "R1") (pin "1") (pinfunction "1_1") (pintype "passive"))
    )
    (net (code "64") (name "unconnected-(IO1-NFAULT-Pad16)") (class "Default")
      (node (ref "IO1") (pin "16") (pinfunction "NFAULT_16") (pintype "bidirectional"))
    )
    (net (code "65") (name "unconnected-(LSM6DS0-DRDY{slash}INT2-PadP$6)") (class "Default")
      (node (ref "LSM6DS0") (pin "P$6") (pinfunction "DRDY/INT2_P$6") (pintype "bidirectional"))
    )
    (net (code "66") (name "unconnected-(LSM6DS0-INT1-PadP$7)") (class "Default")
      (node (ref "LSM6DS0") (pin "P$7") (pinfunction "INT1_P$7") (pintype "bidirectional"))
    )
    (net (code "67") (name "unconnected-(U4A-PB1-Pad27)") (class "Default")
      (node (ref "U4") (pin "27") (pinfunction "PB1_27") (pintype "bidirectional"))
    )
    (net (code "68") (name "unconnected-(U4A-PB10-Pad29)") (class "Default")
      (node (ref "U4") (pin "29") (pinfunction "PB10_29") (pintype "bidirectional"))
    )
    (net (code "69") (name "unconnected-(U4A-PB11-Pad30)") (class "Default")
      (node (ref "U4") (pin "30") (pinfunction "PB11_30") (pintype "bidirectional"))
    )
    (net (code "70") (name "unconnected-(U4A-PC0-Pad8)") (class "Default")
      (node (ref "U4") (pin "8") (pinfunction "PC0_8") (pintype "bidirectional"))
    )
    (net (code "71") (name "unconnected-(U4A-PC1-Pad9)") (class "Default")
      (node (ref "U4") (pin "9") (pinfunction "PC1_9") (pintype "bidirectional"))
    )
    (net (code "72") (name "unconnected-(U4A-PC2-Pad10)") (class "Default")
      (node (ref "U4") (pin "10") (pinfunction "PC2_10") (pintype "bidirectional"))
    )
    (net (code "73") (name "unconnected-(U4A-PC3-Pad11)") (class "Default")
      (node (ref "U4") (pin "11") (pinfunction "PC3_11") (pintype "bidirectional"))
    )
    (net (code "74") (name "unconnected-(U4A-PC4-Pad24)") (class "Default")
      (node (ref "U4") (pin "24") (pinfunction "PC4_24") (pintype "bidirectional"))
    )
    (net (code "75") (name "unconnected-(U4A-PC5-Pad25)") (class "Default")
      (node (ref "U4") (pin "25") (pinfunction "PC5_25") (pintype "bidirectional"))
    )
    (net (code "76") (name "unconnected-(U4A-PC14-OSC32_IN-Pad3)") (class "Default")
      (node (ref "U4") (pin "3") (pinfunction "PC14-OSC32_IN_3") (pintype "bidirectional"))
    )
    (net (code "77") (name "unconnected-(U4A-PC15-OSC32_OUT-Pad4)") (class "Default")
      (node (ref "U4") (pin "4") (pinfunction "PC15-OSC32_OUT_4") (pintype "bidirectional"))
    )
    (net (code "78") (name "unconnected-(U4A-PF4-Pad18)") (class "Default")
      (node (ref "U4") (pin "18") (pinfunction "PF4_18") (pintype "bidirectional"))
    )
    (net (code "79") (name "unconnected-(U4B-PB3-Pad55)") (class "Default")
      (node (ref "U4") (pin "55") (pinfunction "PB3_55") (pintype "bidirectional"))
    )
    (net (code "80") (name "unconnected-(U4B-PB8-Pad61)") (class "Default")
      (node (ref "U4") (pin "61") (pinfunction "PB8_61") (pintype "bidirectional"))
    )
    (net (code "81") (name "unconnected-(U4B-PB9-Pad62)") (class "Default")
      (node (ref "U4") (pin "62") (pinfunction "PB9_62") (pintype "bidirectional"))
    )
    (net (code "82") (name "unconnected-(U4B-PC8-Pad39)") (class "Default")
      (node (ref "U4") (pin "39") (pinfunction "PC8_39") (pintype "bidirectional"))
    )
    (net (code "83") (name "unconnected-(U4B-PC9-Pad40)") (class "Default")
      (node (ref "U4") (pin "40") (pinfunction "PC9_40") (pintype "bidirectional"))
    )
    (net (code "84") (name "unconnected-(U4B-PC10-Pad51)") (class "Default")
      (node (ref "U4") (pin "51") (pinfunction "PC10_51") (pintype "bidirectional"))
    )
    (net (code "85") (name "unconnected-(U4B-PD2-Pad54)") (class "Default")
      (node (ref "U4") (pin "54") (pinfunction "PD2_54") (pintype "bidirectional"))
    )
    (net (code "86") (name "unconnected-(USER-Pad4)") (class "Default")
      (node (ref "USER") (pin "4") (pinfunction "4_4") (pintype "passive"))
    )
    (net (code "87") (name "unconnected-(X1-Pad4)") (class "Default")
      (node (ref "X1") (pin "4") (pinfunction "4_4") (pintype "passive"))
    )
  )
)
